# untitled3.net
KiCad netlist of a schematic drawn in EAGLE
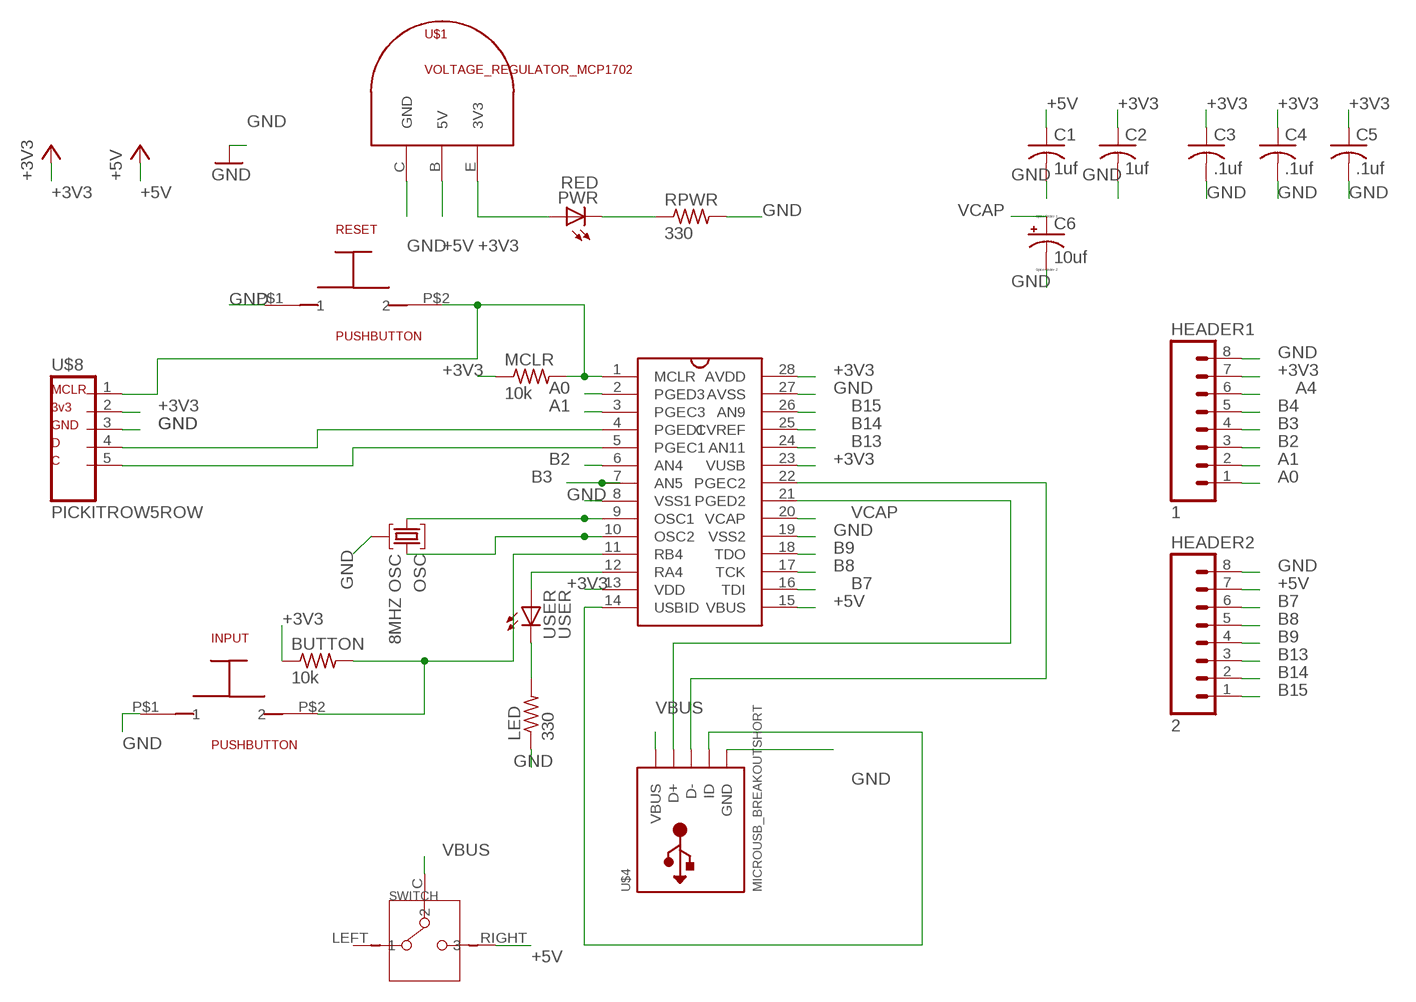
[diagram p0: schematic, sheet 1]

(export (version "E")
  (design (tool "Eeschema 10.0.6"))
  (components
    (comp (ref "BUTTON")
      (value "10k")
      (footprint "eagle-import:0207_10")
      (libsource (lib "eagle-import") (part "R-US_0207/10"))
    )
    (comp (ref "C1")
      (value "1uf")
      (footprint "eagle-import:C025-030X050")
      (libsource (lib "eagle-import") (part "C-US025-030X050"))
    )
    (comp (ref "C2")
      (value "1uf")
      (footprint "eagle-import:C025-030X050")
      (libsource (lib "eagle-import") (part "C-US025-030X050"))
    )
    (comp (ref "C3")
      (value ".1uf")
      (footprint "eagle-import:C025-030X050")
      (libsource (lib "eagle-import") (part "C-US025-030X050"))
    )
    (comp (ref "C4")
      (value ".1uf")
      (footprint "eagle-import:C025-030X050")
      (libsource (lib "eagle-import") (part "C-US025-030X050"))
    )
    (comp (ref "C5")
      (value ".1uf")
      (footprint "eagle-import:C025-030X050")
      (libsource (lib "eagle-import") (part "C-US025-030X050"))
    )
    (comp (ref "C6")
      (value "10uf")
      (footprint "eagle-import:C025-040X050POL")
      (libsource (lib "eagle-import") (part "CAP_TANT_10UFSHORT"))
    )
    (comp (ref "HEADER1")
      (value "1")
      (footprint "eagle-import:1X08_ROUND")
      (libsource (lib "eagle-import") (part "M08"))
    )
    (comp (ref "HEADER2")
      (value "2")
      (footprint "eagle-import:1X08_ROUND")
      (libsource (lib "eagle-import") (part "M08"))
    )
    (comp (ref "INPUT")
      (value "PUSHBUTTON")
      (footprint "eagle-import:PUSHBUTTON")
      (libsource (lib "eagle-import") (part "PUSHBUTTON"))
    )
    (comp (ref "LED")
      (value "330")
      (footprint "eagle-import:0207_10")
      (libsource (lib "eagle-import") (part "R-US_0207/10"))
    )
    (comp (ref "MCLR")
      (value "10k")
      (footprint "eagle-import:0207_10")
      (libsource (lib "eagle-import") (part "R-US_0207/10"))
    )
    (comp (ref "OSC")
      (value "8MHZ OSC")
      (footprint "eagle-import:CRYSTAL_8MHZ")
      (libsource (lib "eagle-import") (part "CRYSTAL_8MHZ"))
    )
    (comp (ref "PWR")
      (value "RED")
      (footprint "eagle-import:LED3MM")
      (libsource (lib "eagle-import") (part "LED3MM"))
    )
    (comp (ref "RESET")
      (value "PUSHBUTTON")
      (footprint "eagle-import:PUSHBUTTON")
      (libsource (lib "eagle-import") (part "PUSHBUTTON"))
    )
    (comp (ref "RPWR")
      (value "330")
      (footprint "eagle-import:0207_10")
      (libsource (lib "eagle-import") (part "R-US_0207/10"))
    )
    (comp (ref "SWITCH")
      (value "DIP-SLIDE-SWITCH(3P-11.6X4.0X5.4+2.0MM)-EG1218")
      (footprint "eagle-import:SW3-2.5-11.6X4.0X5.4+2.0MM")
      (libsource (lib "eagle-import") (part "DIP-SLIDE-SWITCH(3P-11.6X4.0X5.4+2.0MM)-EG1218"))
    )
    (comp (ref "U$1")
      (value "VOLTAGE_REGULATOR_MCP1702")
      (footprint "eagle-import:TO92-EBC")
      (libsource (lib "eagle-import") (part "VOLTAGE_REGULATOR_MCP1702"))
    )
    (comp (ref "U$4")
      (value "MICROUSB_BREAKOUTSHORT")
      (footprint "eagle-import:USB-MB-SHORT")
      (libsource (lib "eagle-import") (part "MICROUSB_BREAKOUTSHORT"))
    )
    (comp (ref "U$5")
      (value "PIC32MX250F128B")
      (footprint "eagle-import:DIL28-3")
      (libsource (lib "eagle-import") (part "PIC32MX250F128B"))
    )
    (comp (ref "U$8")
      (value "PICKITROW5ROW")
      (footprint "eagle-import:1X05")
      (libsource (lib "eagle-import") (part "PICKITROW5ROW"))
    )
    (comp (ref "USER")
      (value "USER")
      (footprint "eagle-import:LED3MM")
      (fields (field (name "MF") "VISHAY SEMICONDUCTOR"))
      (libsource (lib "eagle-import") (part "TLLG4400"))
    )
  )
  (nets
    (net (code "1") (name "+3V3") (class "Default")
      (node (ref "BUTTON") (pin "1") (pinfunction "1_1") (pintype "passive"))
      (node (ref "C2") (pin "1") (pinfunction "1_1") (pintype "passive"))
      (node (ref "C3") (pin "1") (pinfunction "1_1") (pintype "passive"))
      (node (ref "C4") (pin "1") (pinfunction "1_1") (pintype "passive"))
      (node (ref "C5") (pin "1") (pinfunction "1_1") (pintype "passive"))
      (node (ref "HEADER1") (pin "7") (pinfunction "7_7") (pintype "passive"))
      (node (ref "MCLR") (pin "1") (pinfunction "1_1") (pintype "passive"))
      (node (ref "PWR") (pin "A") (pinfunction "A_A") (pintype "passive"))
      (node (ref "U$1") (pin "E") (pinfunction "3V3_E") (pintype "bidirectional"))
      (node (ref "U$5") (pin "13") (pinfunction "VDD_13") (pintype "bidirectional"))
      (node (ref "U$5") (pin "23") (pinfunction "VUSB_23") (pintype "bidirectional"))
      (node (ref "U$5") (pin "28") (pinfunction "AVDD_28") (pintype "bidirectional"))
      (node (ref "U$8") (pin "2") (pinfunction "3V3_2") (pintype "passive"))
    )
    (net (code "2") (name "+5V") (class "Default")
      (node (ref "C1") (pin "1") (pinfunction "1_1") (pintype "passive"))
      (node (ref "HEADER2") (pin "7") (pinfunction "7_7") (pintype "passive"))
      (node (ref "SWITCH") (pin "RIGHT") (pinfunction "3_RIGHT") (pintype "bidirectional"))
      (node (ref "U$1") (pin "B") (pinfunction "5V_B") (pintype "bidirectional"))
      (node (ref "U$5") (pin "15") (pinfunction "VBUS_15") (pintype "bidirectional"))
    )
    (net (code "3") (name "/A0") (class "Default")
      (node (ref "HEADER1") (pin "1") (pinfunction "1_1") (pintype "passive"))
      (node (ref "U$5") (pin "2") (pinfunction "PGED3_2") (pintype "bidirectional"))
    )
    (net (code "4") (name "/A1") (class "Default")
      (node (ref "HEADER1") (pin "2") (pinfunction "2_2") (pintype "passive"))
      (node (ref "U$5") (pin "3") (pinfunction "PGEC3_3") (pintype "bidirectional"))
    )
    (net (code "5") (name "/A4") (class "Default")
      (node (ref "HEADER1") (pin "6") (pinfunction "6_6") (pintype "passive"))
      (node (ref "U$5") (pin "12") (pinfunction "RA4_12") (pintype "bidirectional"))
      (node (ref "USER") (pin "A") (pinfunction "A_A") (pintype "passive"))
    )
    (net (code "6") (name "/B2") (class "Default")
      (node (ref "HEADER1") (pin "3") (pinfunction "3_3") (pintype "passive"))
      (node (ref "U$5") (pin "6") (pinfunction "AN4_6") (pintype "bidirectional"))
    )
    (net (code "7") (name "/B3") (class "Default")
      (node (ref "HEADER1") (pin "4") (pinfunction "4_4") (pintype "passive"))
      (node (ref "U$5") (pin "7") (pinfunction "AN5_7") (pintype "bidirectional"))
    )
    (net (code "8") (name "/B4") (class "Default")
      (node (ref "BUTTON") (pin "2") (pinfunction "2_2") (pintype "passive"))
      (node (ref "HEADER1") (pin "5") (pinfunction "5_5") (pintype "passive"))
      (node (ref "INPUT") (pin "P$2") (pinfunction "2_P$2") (pintype "bidirectional"))
      (node (ref "U$5") (pin "11") (pinfunction "RB4_11") (pintype "bidirectional"))
    )
    (net (code "9") (name "/B7") (class "Default")
      (node (ref "HEADER2") (pin "6") (pinfunction "6_6") (pintype "passive"))
      (node (ref "U$5") (pin "16") (pinfunction "TDI_16") (pintype "bidirectional"))
    )
    (net (code "10") (name "/B8") (class "Default")
      (node (ref "HEADER2") (pin "5") (pinfunction "5_5") (pintype "passive"))
      (node (ref "U$5") (pin "17") (pinfunction "TCK_17") (pintype "bidirectional"))
    )
    (net (code "11") (name "/B9") (class "Default")
      (node (ref "HEADER2") (pin "4") (pinfunction "4_4") (pintype "passive"))
      (node (ref "U$5") (pin "18") (pinfunction "TDO_18") (pintype "bidirectional"))
    )
    (net (code "12") (name "/B13") (class "Default")
      (node (ref "HEADER2") (pin "3") (pinfunction "3_3") (pintype "passive"))
      (node (ref "U$5") (pin "24") (pinfunction "AN11_24") (pintype "bidirectional"))
    )
    (net (code "13") (name "/B14") (class "Default")
      (node (ref "HEADER2") (pin "2") (pinfunction "2_2") (pintype "passive"))
      (node (ref "U$5") (pin "25") (pinfunction "CVREF_25") (pintype "bidirectional"))
    )
    (net (code "14") (name "/B15") (class "Default")
      (node (ref "HEADER2") (pin "1") (pinfunction "1_1") (pintype "passive"))
      (node (ref "U$5") (pin "26") (pinfunction "AN9_26") (pintype "bidirectional"))
    )
    (net (code "15") (name "/VBUS") (class "Default")
      (node (ref "SWITCH") (pin "C") (pinfunction "2_C") (pintype "bidirectional"))
      (node (ref "U$4") (pin "VBUS") (pinfunction "VBUS_VBUS") (pintype "power_in"))
    )
    (net (code "16") (name "/VCAP") (class "Default")
      (node (ref "C6") (pin "+") (pinfunction "+_+") (pintype "passive"))
      (node (ref "U$5") (pin "20") (pinfunction "VCAP_20") (pintype "bidirectional"))
    )
    (net (code "17") (name "GND") (class "Default")
      (node (ref "C1") (pin "2") (pinfunction "2_2") (pintype "passive"))
      (node (ref "C2") (pin "2") (pinfunction "2_2") (pintype "passive"))
      (node (ref "C3") (pin "2") (pinfunction "2_2") (pintype "passive"))
      (node (ref "C4") (pin "2") (pinfunction "2_2") (pintype "passive"))
      (node (ref "C5") (pin "2") (pinfunction "2_2") (pintype "passive"))
      (node (ref "C6") (pin "-") (pinfunction "-_-") (pintype "passive"))
      (node (ref "HEADER1") (pin "8") (pinfunction "8_8") (pintype "passive"))
      (node (ref "HEADER2") (pin "8") (pinfunction "8_8") (pintype "passive"))
      (node (ref "INPUT") (pin "P$1") (pinfunction "1_P$1") (pintype "bidirectional"))
      (node (ref "LED") (pin "1") (pinfunction "1_1") (pintype "passive"))
      (node (ref "OSC") (pin "GND") (pinfunction "2_GND") (pintype "passive"))
      (node (ref "RESET") (pin "P$1") (pinfunction "1_P$1") (pintype "bidirectional"))
      (node (ref "RPWR") (pin "2") (pinfunction "2_2") (pintype "passive"))
      (node (ref "U$1") (pin "C") (pinfunction "GND_C") (pintype "bidirectional"))
      (node (ref "U$4") (pin "GND") (pinfunction "GND_GND") (pintype "power_in"))
      (node (ref "U$5") (pin "19") (pinfunction "VSS2_19") (pintype "bidirectional"))
      (node (ref "U$5") (pin "27") (pinfunction "AVSS_27") (pintype "bidirectional"))
      (node (ref "U$5") (pin "8") (pinfunction "VSS1_8") (pintype "bidirectional"))
      (node (ref "U$8") (pin "3") (pinfunction "GND_3") (pintype "passive"))
    )
    (net (code "18") (name "Net-(OSC-1)") (class "Default")
      (node (ref "OSC") (pin "OSC1") (pinfunction "1_OSC1") (pintype "passive"))
      (node (ref "U$5") (pin "9") (pinfunction "OSC1_9") (pintype "bidirectional"))
    )
    (net (code "19") (name "Net-(OSC-3)") (class "Default")
      (node (ref "OSC") (pin "OSC2") (pinfunction "3_OSC2") (pintype "passive"))
      (node (ref "U$5") (pin "10") (pinfunction "OSC2_10") (pintype "bidirectional"))
    )
    (net (code "20") (name "Net-(PWR-C)") (class "Default")
      (node (ref "PWR") (pin "K") (pinfunction "C_K") (pintype "passive"))
      (node (ref "RPWR") (pin "1") (pinfunction "1_1") (pintype "passive"))
    )
    (net (code "21") (name "Net-(RESET-2)") (class "Default")
      (node (ref "MCLR") (pin "2") (pinfunction "2_2") (pintype "passive"))
      (node (ref "RESET") (pin "P$2") (pinfunction "2_P$2") (pintype "bidirectional"))
      (node (ref "U$5") (pin "1") (pinfunction "MCLR_1") (pintype "bidirectional"))
      (node (ref "U$8") (pin "1") (pinfunction "MCLR_1") (pintype "passive"))
    )
    (net (code "22") (name "Net-(U$5-PGEC1)") (class "Default")
      (node (ref "U$5") (pin "5") (pinfunction "PGEC1_5") (pintype "bidirectional"))
      (node (ref "U$8") (pin "5") (pinfunction "C_5") (pintype "passive"))
    )
    (net (code "23") (name "Net-(U$5-PGEC2)") (class "Default")
      (node (ref "U$4") (pin "D-") (pinfunction "D-_D-") (pintype "bidirectional"))
      (node (ref "U$5") (pin "22") (pinfunction "PGEC2_22") (pintype "bidirectional"))
    )
    (net (code "24") (name "Net-(U$5-PGED1)") (class "Default")
      (node (ref "U$5") (pin "4") (pinfunction "PGED1_4") (pintype "bidirectional"))
      (node (ref "U$8") (pin "4") (pinfunction "D_4") (pintype "passive"))
    )
    (net (code "25") (name "Net-(U$5-PGED2)") (class "Default")
      (node (ref "U$4") (pin "D+") (pinfunction "D+_D+") (pintype "bidirectional"))
      (node (ref "U$5") (pin "21") (pinfunction "PGED2_21") (pintype "bidirectional"))
    )
    (net (code "26") (name "Net-(U$5-USBID)") (class "Default")
      (node (ref "U$4") (pin "ID") (pinfunction "ID_ID") (pintype "bidirectional"))
      (node (ref "U$5") (pin "14") (pinfunction "USBID_14") (pintype "bidirectional"))
    )
    (net (code "27") (name "Net-(USER-C)") (class "Default")
      (node (ref "LED") (pin "2") (pinfunction "2_2") (pintype "passive"))
      (node (ref "USER") (pin "K") (pinfunction "C_K") (pintype "passive"))
    )
    (net (code "28") (name "unconnected-(SWITCH-1-PadLEFT)") (class "Default")
      (node (ref "SWITCH") (pin "LEFT") (pinfunction "1_LEFT") (pintype "bidirectional"))
    )
  )
)
